# V1.net
KiCad netlist of a schematic drawn in EAGLE
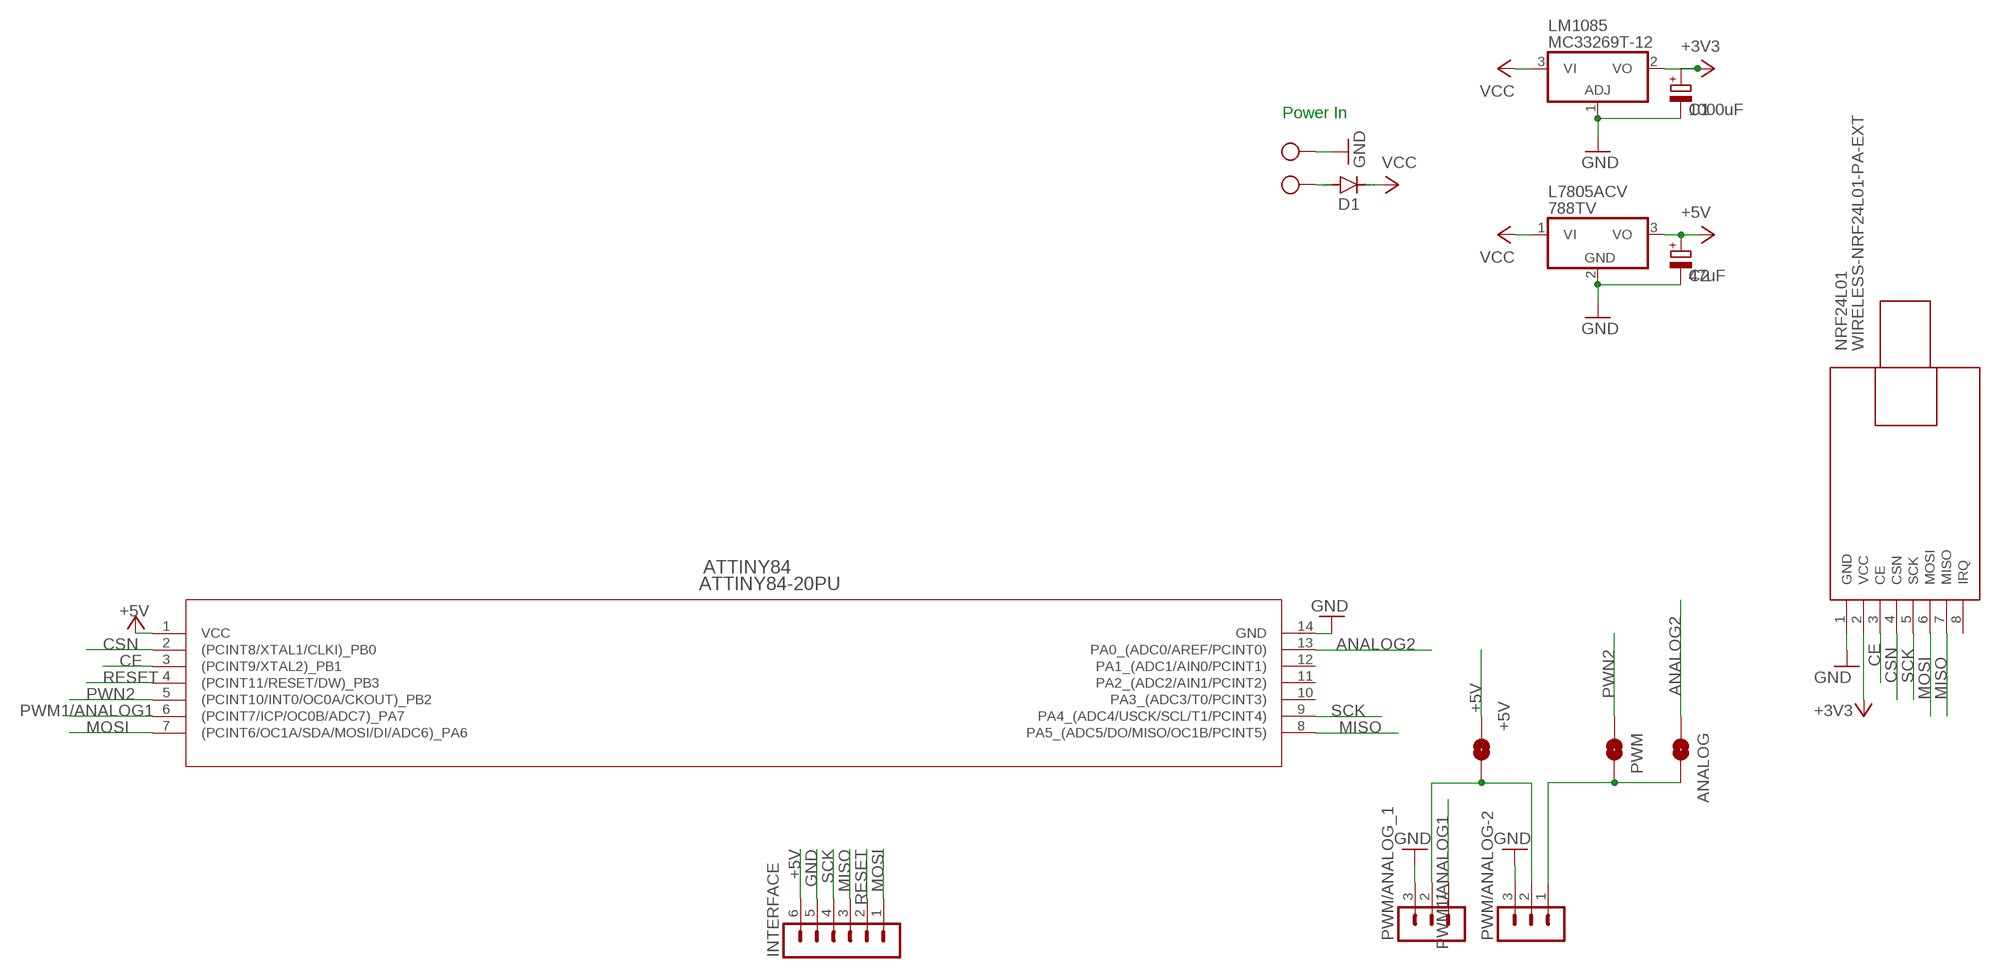
[diagram p0: schematic, sheet 1]

(export (version "E")
  (design (tool "Eeschema 10.0.6"))
  (components
    (comp (ref "+5V")
      (value "JUMPER-SMT_2_NO_NO-SILK")
      (footprint "eagle-import:SMT-JUMPER_2_NO_NO-SILK")
      (libsource (lib "eagle-import") (part "JUMPER-SMT_2_NO_NO-SILK"))
    )
    (comp (ref "ANALOG")
      (value "JUMPER-SMT_2_NO_NO-SILK")
      (footprint "eagle-import:SMT-JUMPER_2_NO_NO-SILK")
      (libsource (lib "eagle-import") (part "JUMPER-SMT_2_NO_NO-SILK"))
    )
    (comp (ref "ATTINY84")
      (value "ATTINY84-20PU")
      (footprint "eagle-import:14P3")
      (fields (field (name "MANUFACTURER_PART_NUMBER") "ATTINY8420PU"))
      (libsource (lib "eagle-import") (part "ATTINY84-20PU"))
    )
    (comp (ref "C1")
      (value "1000uF")
      (footprint "eagle-import:E2,5-6")
      (libsource (lib "eagle-import") (part "CPOL-EUE2.5-6"))
    )
    (comp (ref "C2")
      (value "47uF")
      (footprint "eagle-import:E2,5-6")
      (libsource (lib "eagle-import") (part "CPOL-EUE2.5-6"))
    )
    (comp (ref "D1")
      (value "1N5060GP")
      (footprint "eagle-import:DO15-12")
      (libsource (lib "eagle-import") (part "1N5060GP"))
    )
    (comp (ref "INTERFACE")
      (value "MA06-1")
      (footprint "eagle-import:MA06-1")
      (libsource (lib "eagle-import") (part "MA06-1"))
    )
    (comp (ref "L7805ACV")
      (value "788TV")
      (footprint "eagle-import:TO220V")
      (libsource (lib "eagle-import") (part "78TV8"))
    )
    (comp (ref "LM1085")
      (value "MC33269T-12")
      (footprint "eagle-import:TO220V")
      (libsource (lib "eagle-import") (part "MC33269?T-12"))
    )
    (comp (ref "NRF24L01")
      (value "WIRELESS-NRF24L01-PA-EXT")
      (footprint "eagle-import:WIRELESS-NRF24L01-PA-EXT")
      (libsource (lib "eagle-import") (part "WIRELESS-NRF24L01-PA-EXT"))
    )
    (comp (ref "PWM")
      (value "JUMPER-SMT_2_NO_NO-SILK")
      (footprint "eagle-import:SMT-JUMPER_2_NO_NO-SILK")
      (libsource (lib "eagle-import") (part "JUMPER-SMT_2_NO_NO-SILK"))
    )
    (comp (ref "PWM/ANALOG-2")
      (value "MA03-1")
      (footprint "eagle-import:MA03-1")
      (libsource (lib "eagle-import") (part "MA03-1"))
    )
    (comp (ref "PWM/ANALOG_1")
      (value "MA03-1")
      (footprint "eagle-import:MA03-1")
      (libsource (lib "eagle-import") (part "MA03-1"))
    )
    (comp (ref "X1")
      (value "MKDSN1,5/2-5,08")
      (footprint "eagle-import:MKDSN1,5_2-5,08")
      (libsource (lib "eagle-import") (part "MKDSN1,5/2-5,08"))
    )
  )
  (nets
    (net (code "1") (name "+3V3") (class "Default")
      (node (ref "C1") (pin "+") (pinfunction "+_+") (pintype "passive"))
      (node (ref "LM1085") (pin "2") (pinfunction "VO_2") (pintype "passive"))
      (node (ref "NRF24L01") (pin "2") (pinfunction "VCC_2") (pintype "power_in"))
    )
    (net (code "2") (name "+5V") (class "Default")
      (node (ref "+5V") (pin "1") (pinfunction "1_1") (pintype "passive"))
      (node (ref "ATTINY84") (pin "1") (pinfunction "VCC_1") (pintype "power_in"))
      (node (ref "C2") (pin "+") (pinfunction "+_+") (pintype "passive"))
      (node (ref "INTERFACE") (pin "6") (pinfunction "6_6") (pintype "passive"))
      (node (ref "L7805ACV") (pin "3") (pinfunction "VO_3") (pintype "passive"))
    )
    (net (code "3") (name "/ANALOG2") (class "Default")
      (node (ref "ANALOG") (pin "1") (pinfunction "1_1") (pintype "passive"))
      (node (ref "ATTINY84") (pin "13") (pinfunction "PA0_(ADC0/AREF/PCINT0)_13") (pintype "bidirectional"))
    )
    (net (code "4") (name "/CE") (class "Default")
      (node (ref "ATTINY84") (pin "3") (pinfunction "(PCINT9/XTAL2)_PB1_3") (pintype "bidirectional"))
      (node (ref "NRF24L01") (pin "3") (pinfunction "CE_3") (pintype "bidirectional"))
    )
    (net (code "5") (name "/CSN") (class "Default")
      (node (ref "ATTINY84") (pin "2") (pinfunction "(PCINT8/XTAL1/CLKI)_PB0_2") (pintype "bidirectional"))
      (node (ref "NRF24L01") (pin "4") (pinfunction "CSN_4") (pintype "bidirectional"))
    )
    (net (code "6") (name "/MISO") (class "Default")
      (node (ref "ATTINY84") (pin "8") (pinfunction "PA5_(ADC5/DO/MISO/OC1B/PCINT5)_8") (pintype "bidirectional"))
      (node (ref "INTERFACE") (pin "3") (pinfunction "3_3") (pintype "passive"))
      (node (ref "NRF24L01") (pin "7") (pinfunction "MISO_7") (pintype "bidirectional"))
    )
    (net (code "7") (name "/MOSI") (class "Default")
      (node (ref "ATTINY84") (pin "7") (pinfunction "(PCINT6/OC1A/SDA/MOSI/DI/ADC6)_PA6_7") (pintype "bidirectional"))
      (node (ref "INTERFACE") (pin "1") (pinfunction "1_1") (pintype "passive"))
      (node (ref "NRF24L01") (pin "6") (pinfunction "MOSI_6") (pintype "bidirectional"))
    )
    (net (code "8") (name "/PWM1{slash}ANALOG1") (class "Default")
      (node (ref "ATTINY84") (pin "6") (pinfunction "(PCINT7/ICP/OC0B/ADC7)_PA7_6") (pintype "bidirectional"))
      (node (ref "PWM/ANALOG_1") (pin "1") (pinfunction "1_1") (pintype "passive"))
    )
    (net (code "9") (name "/PWN2") (class "Default")
      (node (ref "ATTINY84") (pin "5") (pinfunction "(PCINT10/INT0/OC0A/CKOUT)_PB2_5") (pintype "bidirectional"))
      (node (ref "PWM") (pin "1") (pinfunction "1_1") (pintype "passive"))
    )
    (net (code "10") (name "/RESET") (class "Default")
      (node (ref "ATTINY84") (pin "4") (pinfunction "(PCINT11/RESET/DW)_PB3_4") (pintype "bidirectional"))
      (node (ref "INTERFACE") (pin "2") (pinfunction "2_2") (pintype "passive"))
    )
    (net (code "11") (name "/SCK") (class "Default")
      (node (ref "ATTINY84") (pin "9") (pinfunction "PA4_(ADC4/USCK/SCL/T1/PCINT4)_9") (pintype "bidirectional"))
      (node (ref "INTERFACE") (pin "4") (pinfunction "4_4") (pintype "passive"))
      (node (ref "NRF24L01") (pin "5") (pinfunction "SCK_5") (pintype "bidirectional"))
    )
    (net (code "12") (name "GND") (class "Default")
      (node (ref "ATTINY84") (pin "14") (pinfunction "GND_14") (pintype "power_in"))
      (node (ref "C1") (pin "-") (pinfunction "-_-") (pintype "passive"))
      (node (ref "C2") (pin "-") (pinfunction "-_-") (pintype "passive"))
      (node (ref "INTERFACE") (pin "5") (pinfunction "5_5") (pintype "passive"))
      (node (ref "L7805ACV") (pin "2") (pinfunction "GND_2") (pintype "passive"))
      (node (ref "LM1085") (pin "1") (pinfunction "ADJ_1") (pintype "input"))
      (node (ref "NRF24L01") (pin "1") (pinfunction "GND_1") (pintype "power_in"))
      (node (ref "PWM/ANALOG-2") (pin "3") (pinfunction "3_3") (pintype "passive"))
      (node (ref "PWM/ANALOG_1") (pin "3") (pinfunction "3_3") (pintype "passive"))
      (node (ref "X1") (pin "2") (pinfunction "KL_2") (pintype "passive"))
    )
    (net (code "13") (name "Net-(+5V-Pad2)") (class "Default")
      (node (ref "+5V") (pin "2") (pinfunction "2_2") (pintype "passive"))
      (node (ref "PWM/ANALOG-2") (pin "2") (pinfunction "2_2") (pintype "passive"))
      (node (ref "PWM/ANALOG_1") (pin "2") (pinfunction "2_2") (pintype "passive"))
    )
    (net (code "14") (name "Net-(ANALOG-Pad2)") (class "Default")
      (node (ref "ANALOG") (pin "2") (pinfunction "2_2") (pintype "passive"))
      (node (ref "PWM") (pin "2") (pinfunction "2_2") (pintype "passive"))
      (node (ref "PWM/ANALOG-2") (pin "1") (pinfunction "1_1") (pintype "passive"))
    )
    (net (code "15") (name "Net-(X1A-KL)") (class "Default")
      (node (ref "D1") (pin "A") (pinfunction "A_A") (pintype "passive"))
      (node (ref "X1") (pin "1") (pinfunction "KL_1") (pintype "passive"))
    )
    (net (code "16") (name "VCC") (class "Default")
      (node (ref "D1") (pin "C") (pinfunction "C_C") (pintype "passive"))
      (node (ref "L7805ACV") (pin "1") (pinfunction "VI_1") (pintype "input"))
      (node (ref "LM1085") (pin "3") (pinfunction "VI_3") (pintype "input"))
    )
    (net (code "17") (name "unconnected-(ATTINY84-PA1_(ADC1{slash}AIN0{slash}PCINT1)-Pad12)") (class "Default")
      (node (ref "ATTINY84") (pin "12") (pinfunction "PA1_(ADC1/AIN0/PCINT1)_12") (pintype "bidirectional"))
    )
    (net (code "18") (name "unconnected-(ATTINY84-PA2_(ADC2{slash}AIN1{slash}PCINT2)-Pad11)") (class "Default")
      (node (ref "ATTINY84") (pin "11") (pinfunction "PA2_(ADC2/AIN1/PCINT2)_11") (pintype "bidirectional"))
    )
    (net (code "19") (name "unconnected-(ATTINY84-PA3_(ADC3{slash}T0{slash}PCINT3)-Pad10)") (class "Default")
      (node (ref "ATTINY84") (pin "10") (pinfunction "PA3_(ADC3/T0/PCINT3)_10") (pintype "bidirectional"))
    )
    (net (code "20") (name "unconnected-(NRF24L01-IRQ-Pad8)") (class "Default")
      (node (ref "NRF24L01") (pin "8") (pinfunction "IRQ_8") (pintype "bidirectional"))
    )
  )
)
